# PROC106B_FLASH_USB_TO_UART.net
KiCad netlist of a schematic drawn in Altium Designer
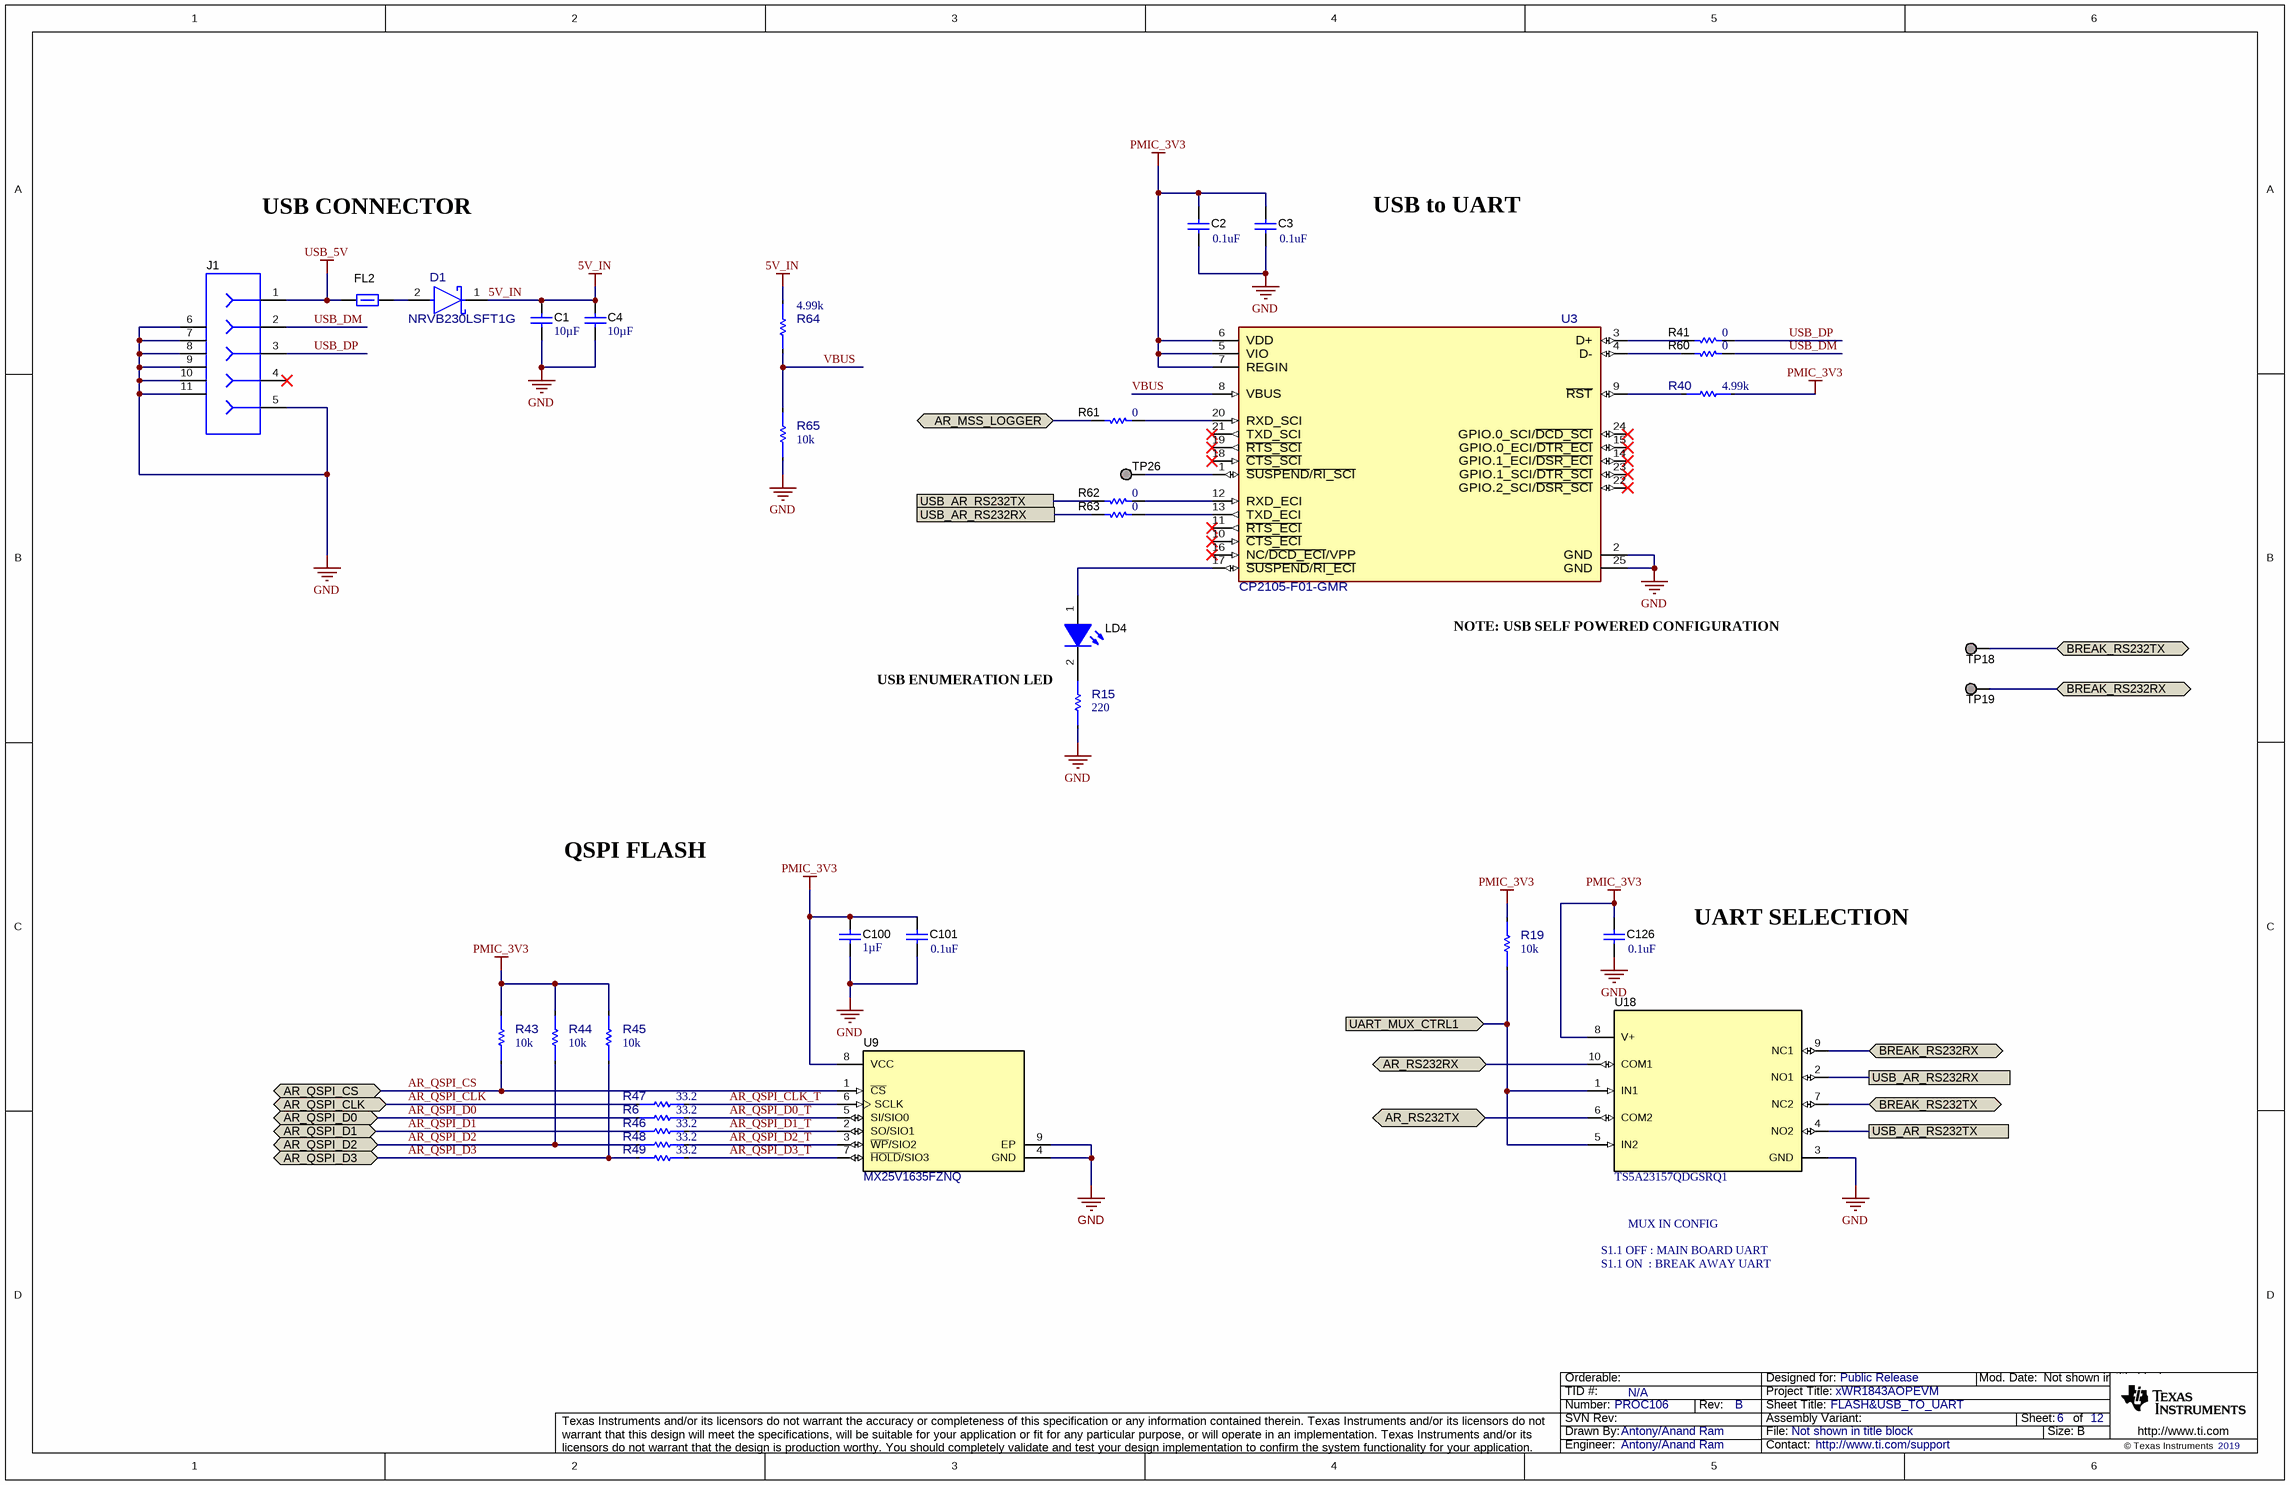
[diagram p0: PROC106B_FLASH_USB_TO_UART.SchDoc]

(export (version "E")
  (design (tool "Eeschema 10.0.6"))
  (components
    (comp (ref "C1")
      (value "GCM21BR71A106KE22L")
      (footprint "0805L")
      (description "CAP, CERM, 10 uF, 10 V, +/- 10%, X7R, 0805")
      (fields
        (field (name "CAP_F") "10µF")
        (field (name "MANUFACTURER") "MuRata")
        (field (name "PUBLISHER") "Texas Instruments")
      )
      (libsource (lib "Altium Vault - TI") (part "Capacitor"))
    )
    (comp (ref "C2")
      (value "GCM155R71C104KA55D")
      (footprint "0402L")
      (description "CAP, CERM, 0.1 uF, 16 V, +/- 10%, X7R, 0402")
      (fields
        (field (name "MANUFACTURER") "MuRata")
        (field (name "VALUEDISPLAYED") "0.1uF")
        (field (name "PUBLISHER") "Texas Instruments")
      )
      (libsource (lib "Altium Vault - TI") (part "Capacitor"))
    )
    (comp (ref "C3")
      (value "GCM155R71C104KA55D")
      (footprint "0402L")
      (description "CAP, CERM, 0.1 uF, 16 V, +/- 10%, X7R, 0402")
      (fields
        (field (name "MANUFACTURER") "MuRata")
        (field (name "VALUEDISPLAYED") "0.1uF")
        (field (name "PUBLISHER") "Texas Instruments")
      )
      (libsource (lib "Altium Vault - TI") (part "Capacitor"))
    )
    (comp (ref "C4")
      (value "GCM21BR71A106KE22L")
      (footprint "0805L")
      (description "CAP, CERM, 10 uF, 10 V, +/- 10%, X7R, 0805")
      (fields
        (field (name "CAP_F") "10µF")
        (field (name "MANUFACTURER") "MuRata")
        (field (name "PUBLISHER") "Texas Instruments")
      )
      (libsource (lib "Altium Vault - TI") (part "Capacitor"))
    )
    (comp (ref "C100")
      (value "GCM188R71C105KA64D")
      (footprint "0603L")
      (description "CAP, CERM, 1 uF, 16 V, +/- 10%, X7R, AEC-Q200 Grade 1, 0603")
      (fields
        (field (name "CAP_F") "1µF")
        (field (name "MANUFACTURER") "MuRata")
        (field (name "PUBLISHER") "Texas Instruments")
      )
      (libsource (lib "Altium Vault - TI") (part "Capacitor"))
    )
    (comp (ref "C101")
      (value "GCM155R71C104KA55D")
      (footprint "0402L")
      (description "CAP, CERM, 0.1 uF, 16 V, +/- 10%, X7R, 0402")
      (fields
        (field (name "MANUFACTURER") "MuRata")
        (field (name "VALUEDISPLAYED") "0.1uF")
        (field (name "PUBLISHER") "Texas Instruments")
      )
      (libsource (lib "Altium Vault - TI") (part "Capacitor"))
    )
    (comp (ref "C126")
      (value "GCM155R71C104KA55D")
      (footprint "0402L")
      (description "CAP, CERM, 0.1 uF, 16 V, +/- 10%, X7R, 0402")
      (fields
        (field (name "MANUFACTURER") "MuRata")
        (field (name "VALUEDISPLAYED") "0.1uF")
        (field (name "PUBLISHER") "Texas Instruments")
      )
      (libsource (lib "Altium Vault - TI") (part "Capacitor"))
    )
    (comp (ref "D1")
      (value "NRVB230LSFT1G")
      (footprint "FP-NRVB230LSFT1G_SOD-123F-MFG")
      (description "Diode Schottky 30V 2A Surface Mount SOD-123FL")
      (fields
        (field (name "MANUFACTURER") "ON Semiconductor")
        (field (name "DIGIKEY PART NUMBER") "NRVB230LSFT1GOSCT-ND")
      )
      (libsource (lib "Altium Vault - TI") (part "SYM-NRVB230LSFT1G"))
    )
    (comp (ref "FL2")
      (value "BLM15PD300SZ1D")
      (footprint "0402L")
      (description "Inductor, Ferrite Bead, Ferrite, 2.2 A, 0.035 ohm, AEC-Q200 Grade 1, SMD")
      (fields (field (name "MANUFACTURER") "MuRata") (field (name "PUBLISHER") "Texas Instruments"))
      (libsource (lib "Altium Vault - TI") (part "Ferrite_Bead"))
    )
    (comp (ref "J1")
      (value "105017-0001")
      (footprint "CONN_105017-0001")
      (description "Connector, Receptacle, Micro-USB Type B, R/A, Bottom Mount SMT")
      (fields (field (name "MANUFACTURER") "Molex") (field (name "PUBLISHER") "Texas Instruments"))
      (libsource (lib "Altium Vault - TI") (part "CONN_105017-0001"))
    )
    (comp (ref "LD4")
      (value "APHHS1005CGCK")
      (footprint "APHHS1005_Green")
      (description "LED, Green, SMD")
      (fields (field (name "MANUFACTURER") "Kingbright"))
      (libsource (lib "Altium Vault - TI") (part "LED"))
    )
    (comp (ref "R6")
      (value "33.2")
      (footprint "FP-ERJ-1GNF33R2C_0201-IPC_C")
      (description "Res Thick Film 0201 33.2 Ohm 1% 0.05W(1/20W) ±200ppm/C Pad SMD Automotive T/R")
      (fields (field (name "MANUFACTURER") "Panasonic") (field (name "PARTNUMBER") "ERJ-1GNF33R2C"))
      (libsource (lib "Altium Vault - TI") (part "SYM-ERJ-1GNF33R2C"))
    )
    (comp (ref "R15")
      (value "220")
      (footprint "FP-ERJ-1GNJ221C_0201-IPC_C")
      (description "220 Ohms ±5% 0.05W, 1/20W Chip Resistor 0201 (0603 Metric) Automotive AEC-Q200 Thick Film")
      (fields
        (field (name "MANUFACTURER") "Panasonic Electronic Components")
        (field (name "PARTNUMBER") "ERJ-1GNJ221C")
      )
      (libsource (lib "Altium Vault - TI") (part "SYM-ERJ-1GNJ221C"))
    )
    (comp (ref "R19")
      (value "10k")
      (footprint "FP-ERA-1AEB103C_0201-IPC_C")
      (description "RES SMD 10K OHM 0.1% 1/20W 0201")
      (fields (field (name "MANUFACTURER") "Panasonic") (field (name "PARTNUMBER") "ERA-1AEB103C"))
      (libsource (lib "Altium Vault - TI") (part "SYM-ERA-1AEB103C"))
    )
    (comp (ref "R40")
      (value "4.99k")
      (footprint "FP-ERJ-1GNF4991C_0201-IPC_C")
      (description "4.99 kOhms ±1% 0.05W, 1/20W Chip Resistor 0201 (0603 Metric) Automotive AEC-Q200 Thick Film")
      (fields
        (field (name "MANUFACTURER") "Panasonic Electronic Components")
        (field (name "PARTNUMBER") "ERJ-1GNF4991C")
      )
      (libsource (lib "Altium Vault - TI") (part "SYM-ERJ-1GNF4991C"))
    )
    (comp (ref "R41")
      (value "ERJ-1GN0R00C")
      (footprint "0201L")
      (description "RES, 0, 5%, .05 W, AEC-Q200 Grade 0, 0201")
      (fields
        (field (name "MANUFACTURER") "Panasonic")
        (field (name "VALUEDISPLAYED") "0")
        (field (name "PUBLISHER") "Texas Instruments")
      )
      (libsource (lib "Altium Vault - TI") (part "Resistor"))
    )
    (comp (ref "R43")
      (value "10k")
      (footprint "FP-ERA-1AEB103C_0201-IPC_C")
      (description "RES SMD 10K OHM 0.1% 1/20W 0201")
      (fields (field (name "MANUFACTURER") "Panasonic") (field (name "PARTNUMBER") "ERA-1AEB103C"))
      (libsource (lib "Altium Vault - TI") (part "SYM-ERA-1AEB103C"))
    )
    (comp (ref "R44")
      (value "10k")
      (footprint "FP-ERA-1AEB103C_0201-IPC_C")
      (description "RES SMD 10K OHM 0.1% 1/20W 0201")
      (fields (field (name "MANUFACTURER") "Panasonic") (field (name "PARTNUMBER") "ERA-1AEB103C"))
      (libsource (lib "Altium Vault - TI") (part "SYM-ERA-1AEB103C"))
    )
    (comp (ref "R45")
      (value "10k")
      (footprint "FP-ERA-1AEB103C_0201-IPC_C")
      (description "RES SMD 10K OHM 0.1% 1/20W 0201")
      (fields (field (name "MANUFACTURER") "Panasonic") (field (name "PARTNUMBER") "ERA-1AEB103C"))
      (libsource (lib "Altium Vault - TI") (part "SYM-ERA-1AEB103C"))
    )
    (comp (ref "R46")
      (value "33.2")
      (footprint "FP-ERJ-1GNF33R2C_0201-IPC_C")
      (description "Res Thick Film 0201 33.2 Ohm 1% 0.05W(1/20W) ±200ppm/C Pad SMD Automotive T/R")
      (fields (field (name "MANUFACTURER") "Panasonic") (field (name "PARTNUMBER") "ERJ-1GNF33R2C"))
      (libsource (lib "Altium Vault - TI") (part "SYM-ERJ-1GNF33R2C"))
    )
    (comp (ref "R47")
      (value "33.2")
      (footprint "FP-ERJ-1GNF33R2C_0201-IPC_C")
      (description "Res Thick Film 0201 33.2 Ohm 1% 0.05W(1/20W) ±200ppm/C Pad SMD Automotive T/R")
      (fields (field (name "MANUFACTURER") "Panasonic") (field (name "PARTNUMBER") "ERJ-1GNF33R2C"))
      (libsource (lib "Altium Vault - TI") (part "SYM-ERJ-1GNF33R2C"))
    )
    (comp (ref "R48")
      (value "33.2")
      (footprint "FP-ERJ-1GNF33R2C_0201-IPC_C")
      (description "Res Thick Film 0201 33.2 Ohm 1% 0.05W(1/20W) ±200ppm/C Pad SMD Automotive T/R")
      (fields (field (name "MANUFACTURER") "Panasonic") (field (name "PARTNUMBER") "ERJ-1GNF33R2C"))
      (libsource (lib "Altium Vault - TI") (part "SYM-ERJ-1GNF33R2C"))
    )
    (comp (ref "R49")
      (value "33.2")
      (footprint "FP-ERJ-1GNF33R2C_0201-IPC_C")
      (description "Res Thick Film 0201 33.2 Ohm 1% 0.05W(1/20W) ±200ppm/C Pad SMD Automotive T/R")
      (fields (field (name "MANUFACTURER") "Panasonic") (field (name "PARTNUMBER") "ERJ-1GNF33R2C"))
      (libsource (lib "Altium Vault - TI") (part "SYM-ERJ-1GNF33R2C"))
    )
    (comp (ref "R60")
      (value "ERJ-1GN0R00C")
      (footprint "0201L")
      (description "RES, 0, 5%, .05 W, AEC-Q200 Grade 0, 0201")
      (fields
        (field (name "MANUFACTURER") "Panasonic")
        (field (name "VALUEDISPLAYED") "0")
        (field (name "PUBLISHER") "Texas Instruments")
      )
      (libsource (lib "Altium Vault - TI") (part "Resistor"))
    )
    (comp (ref "R61")
      (value "ERJ-1GN0R00C")
      (footprint "0201L")
      (description "RES, 0, 5%, .05 W, AEC-Q200 Grade 0, 0201")
      (fields
        (field (name "MANUFACTURER") "Panasonic")
        (field (name "VALUEDISPLAYED") "0")
        (field (name "PUBLISHER") "Texas Instruments")
      )
      (libsource (lib "Altium Vault - TI") (part "Resistor"))
    )
    (comp (ref "R62")
      (value "ERJ-1GN0R00C")
      (footprint "0201L")
      (description "RES, 0, 5%, .05 W, AEC-Q200 Grade 0, 0201")
      (fields
        (field (name "MANUFACTURER") "Panasonic")
        (field (name "VALUEDISPLAYED") "0")
        (field (name "PUBLISHER") "Texas Instruments")
      )
      (libsource (lib "Altium Vault - TI") (part "Resistor"))
    )
    (comp (ref "R63")
      (value "ERJ-1GN0R00C")
      (footprint "0201L")
      (description "RES, 0, 5%, .05 W, AEC-Q200 Grade 0, 0201")
      (fields
        (field (name "MANUFACTURER") "Panasonic")
        (field (name "VALUEDISPLAYED") "0")
        (field (name "PUBLISHER") "Texas Instruments")
      )
      (libsource (lib "Altium Vault - TI") (part "Resistor"))
    )
    (comp (ref "R64")
      (value "4.99k")
      (footprint "FP-ERJ-1GNF4991C_0201-IPC_C")
      (description "4.99 kOhms ±1% 0.05W, 1/20W Chip Resistor 0201 (0603 Metric) Automotive AEC-Q200 Thick Film")
      (fields
        (field (name "MANUFACTURER") "Panasonic Electronic Components")
        (field (name "PARTNUMBER") "ERJ-1GNF4991C")
      )
      (libsource (lib "Altium Vault - TI") (part "SYM-ERJ-1GNF4991C"))
    )
    (comp (ref "R65")
      (value "10k")
      (footprint "FP-ERA-1AEB103C_0201-IPC_C")
      (description "RES SMD 10K OHM 0.1% 1/20W 0201")
      (fields (field (name "MANUFACTURER") "Panasonic") (field (name "PARTNUMBER") "ERA-1AEB103C"))
      (libsource (lib "Altium Vault - TI") (part "SYM-ERA-1AEB103C"))
    )
    (comp (ref "TP18")
      (value "TESTPOINT")
      (footprint "TP_25MIL-SMT")
      (description "TEST POINT.  No entry in BOM.")
      (libsource (lib "Altium Vault - TI") (part "TESTPOINT"))
    )
    (comp (ref "TP19")
      (value "TESTPOINT")
      (footprint "TP_25MIL-SMT")
      (description "TEST POINT.  No entry in BOM.")
      (libsource (lib "Altium Vault - TI") (part "TESTPOINT"))
    )
    (comp (ref "TP26")
      (value "TESTPOINT")
      (footprint "TP_25MIL-SMT")
      (description "TEST POINT.  No entry in BOM.")
      (libsource (lib "Altium Vault - TI") (part "TESTPOINT"))
    )
    (comp (ref "U3")
      (value "CP2105-F01-GMR")
      (footprint "FP-CP2105-F01-GMR_QFN24-EP-IPC_A")
      (description "I/O Controller Interface IC USB to Dual UART bridge")
      (fields (field (name "MANUFACTURER") "Silicon Labs"))
      (libsource (lib "Altium Vault - TI") (part "SYM-CP2105-F01-GMR"))
    )
    (comp (ref "U9")
      (value "MX25V1635FZNQ")
      (footprint "WSON-8L_6x5MM_EP")
      (description "2.3V-3.6V, 16M-BIT [x 1/x 2/x 4] CMOS FLASH Memory, WSON-8")
      (fields (field (name "MANUFACTURER") "Macronix International Co., LTD"))
      (libsource (lib "Altium Vault - TI") (part "MX25V1635FZ"))
    )
    (comp (ref "U18")
      (value "TS5A23157QDGSRQ1")
      (footprint "DGS0010A_L")
      (description "Automotive Catalog Dual 15-Ohm SPDT Analog Switch, DGS0010A (VSSOP-10)")
      (fields
        (field (name "MANUFACTURER") "Texas Instruments")
        (field (name "PARTNUMBER") "TS5A23157QDGSRQ1")
        (field (name "PUBLISHER") "Texas Instruments")
      )
      (libsource (lib "Altium Vault - TI") (part "TS5A23159"))
    )
  )
  (nets
    (net (code "1") (name "/AR_MSS_LOGGER") (class "Default")
      (node (ref "R61") (pin "1") (pinfunction "1_1") (pintype "passive"))
    )
    (net (code "2") (name "/AR_QSPI_CLK") (class "Default")
      (node (ref "R47") (pin "1") (pinfunction "1_1") (pintype "passive"))
    )
    (net (code "3") (name "/AR_QSPI_CLK_T") (class "Default")
      (node (ref "R47") (pin "2") (pinfunction "2_2") (pintype "passive"))
      (node (ref "U9") (pin "6") (pinfunction "SCLK_6") (pintype "input"))
    )
    (net (code "4") (name "/AR_QSPI_CS") (class "Default")
      (node (ref "R43") (pin "1") (pinfunction "1_1") (pintype "passive"))
      (node (ref "U9") (pin "1") (pinfunction "CS_1") (pintype "input"))
    )
    (net (code "5") (name "/AR_QSPI_D0") (class "Default")
      (node (ref "R6") (pin "1") (pinfunction "1_1") (pintype "passive"))
    )
    (net (code "6") (name "/AR_QSPI_D0_T") (class "Default")
      (node (ref "R6") (pin "2") (pinfunction "2_2") (pintype "passive"))
      (node (ref "U9") (pin "5") (pinfunction "SI/SIO0_5") (pintype "bidirectional"))
    )
    (net (code "7") (name "/AR_QSPI_D1") (class "Default")
      (node (ref "R46") (pin "1") (pinfunction "1_1") (pintype "passive"))
    )
    (net (code "8") (name "/AR_QSPI_D1_T") (class "Default")
      (node (ref "R46") (pin "2") (pinfunction "2_2") (pintype "passive"))
      (node (ref "U9") (pin "2") (pinfunction "SO/SIO1_2") (pintype "bidirectional"))
    )
    (net (code "9") (name "/AR_QSPI_D2") (class "Default")
      (node (ref "R44") (pin "1") (pinfunction "1_1") (pintype "passive"))
      (node (ref "R48") (pin "1") (pinfunction "1_1") (pintype "passive"))
    )
    (net (code "10") (name "/AR_QSPI_D2_T") (class "Default")
      (node (ref "R48") (pin "2") (pinfunction "2_2") (pintype "passive"))
      (node (ref "U9") (pin "3") (pinfunction "~{WP}/SIO2_3") (pintype "bidirectional"))
    )
    (net (code "11") (name "/AR_QSPI_D3") (class "Default")
      (node (ref "R45") (pin "1") (pinfunction "1_1") (pintype "passive"))
      (node (ref "R49") (pin "1") (pinfunction "1_1") (pintype "passive"))
    )
    (net (code "12") (name "/AR_QSPI_D3_T") (class "Default")
      (node (ref "R49") (pin "2") (pinfunction "2_2") (pintype "passive"))
      (node (ref "U9") (pin "7") (pinfunction "~{HOLD}/SIO3_7") (pintype "bidirectional"))
    )
    (net (code "13") (name "/AR_RS232RX") (class "Default")
      (node (ref "U18") (pin "10") (pinfunction "COM1_10") (pintype "bidirectional"))
    )
    (net (code "14") (name "/AR_RS232TX") (class "Default")
      (node (ref "U18") (pin "6") (pinfunction "COM2_6") (pintype "bidirectional"))
    )
    (net (code "15") (name "/BREAK_RS232RX") (class "Default")
      (node (ref "TP19") (pin "1") (pintype "passive"))
      (node (ref "U18") (pin "9") (pinfunction "NC1_9") (pintype "bidirectional"))
    )
    (net (code "16") (name "/BREAK_RS232TX") (class "Default")
      (node (ref "TP18") (pin "1") (pintype "passive"))
      (node (ref "U18") (pin "7") (pinfunction "NC2_7") (pintype "bidirectional"))
    )
    (net (code "17") (name "/UART_MUX_CTRL1") (class "Default")
      (node (ref "R19") (pin "1") (pinfunction "1_1") (pintype "passive"))
      (node (ref "U18") (pin "1") (pinfunction "IN1_1") (pintype "input"))
      (node (ref "U18") (pin "5") (pinfunction "IN2_5") (pintype "input"))
    )
    (net (code "18") (name "/USB_AR_RS232RX") (class "Default")
      (node (ref "R63") (pin "1") (pinfunction "1_1") (pintype "passive"))
      (node (ref "U18") (pin "2") (pinfunction "NO1_2") (pintype "bidirectional"))
    )
    (net (code "19") (name "/USB_AR_RS232TX") (class "Default")
      (node (ref "R62") (pin "1") (pinfunction "1_1") (pintype "passive"))
      (node (ref "U18") (pin "4") (pinfunction "NO2_4") (pintype "bidirectional"))
    )
    (net (code "20") (name "/USB_DM") (class "Default")
      (node (ref "J1") (pin "2") (pintype "passive"))
      (node (ref "R60") (pin "2") (pinfunction "2_2") (pintype "passive"))
    )
    (net (code "21") (name "/USB_DP") (class "Default")
      (node (ref "J1") (pin "3") (pintype "passive"))
      (node (ref "R41") (pin "2") (pinfunction "2_2") (pintype "passive"))
    )
    (net (code "22") (name "/VBUS") (class "Default")
      (node (ref "R64") (pin "2") (pinfunction "2_2") (pintype "passive"))
      (node (ref "R65") (pin "2") (pinfunction "2_2") (pintype "passive"))
      (node (ref "U3") (pin "8") (pinfunction "VBUS_8") (pintype "input"))
    )
    (net (code "23") (name "5V_IN") (class "Default")
      (node (ref "C1") (pin "2") (pinfunction "2_2") (pintype "passive"))
      (node (ref "C4") (pin "1") (pinfunction "1_1") (pintype "passive"))
      (node (ref "D1") (pin "1") (pinfunction "CATHODE_1") (pintype "passive"))
      (node (ref "R64") (pin "1") (pinfunction "1_1") (pintype "passive"))
    )
    (net (code "24") (name "GND") (class "Default")
      (node (ref "C1") (pin "1") (pinfunction "1_1") (pintype "passive"))
      (node (ref "C100") (pin "1") (pinfunction "1_1") (pintype "passive"))
      (node (ref "C101") (pin "1") (pinfunction "1_1") (pintype "passive"))
      (node (ref "C126") (pin "1") (pinfunction "1_1") (pintype "passive"))
      (node (ref "C2") (pin "2") (pinfunction "2_2") (pintype "passive"))
      (node (ref "C3") (pin "2") (pinfunction "2_2") (pintype "passive"))
      (node (ref "C4") (pin "2") (pinfunction "2_2") (pintype "passive"))
      (node (ref "J1") (pin "10") (pintype "passive"))
      (node (ref "J1") (pin "11") (pintype "passive"))
      (node (ref "J1") (pin "5") (pintype "passive"))
      (node (ref "J1") (pin "6") (pintype "passive"))
      (node (ref "J1") (pin "7") (pintype "passive"))
      (node (ref "J1") (pin "8") (pintype "passive"))
      (node (ref "J1") (pin "9") (pintype "passive"))
      (node (ref "R15") (pin "1") (pinfunction "1_1") (pintype "passive"))
      (node (ref "R65") (pin "1") (pinfunction "1_1") (pintype "passive"))
      (node (ref "U18") (pin "3") (pinfunction "GND_3") (pintype "power_in"))
      (node (ref "U3") (pin "2") (pinfunction "GND_2") (pintype "power_in"))
      (node (ref "U3") (pin "25") (pinfunction "GND_25") (pintype "power_in"))
      (node (ref "U9") (pin "4") (pinfunction "GND_4") (pintype "power_in"))
      (node (ref "U9") (pin "9") (pinfunction "EP_9") (pintype "passive"))
    )
    (net (code "25") (name "Net-(D1-ANODE)") (class "Default")
      (node (ref "D1") (pin "2") (pinfunction "ANODE_2") (pintype "passive"))
      (node (ref "FL2") (pin "2") (pinfunction "2_2") (pintype "passive"))
    )
    (net (code "26") (name "Net-(LD4-A)") (class "Default")
      (node (ref "LD4") (pin "1") (pinfunction "A_1") (pintype "passive"))
      (node (ref "U3") (pin "17") (pinfunction "~{SUSPEND}/~{RI_ECI}_17") (pintype "bidirectional"))
    )
    (net (code "27") (name "Net-(LD4-K)") (class "Default")
      (node (ref "LD4") (pin "2") (pinfunction "K_2") (pintype "passive"))
      (node (ref "R15") (pin "2") (pinfunction "2_2") (pintype "passive"))
    )
    (net (code "28") (name "Net-(U3-D+)") (class "Default")
      (node (ref "R41") (pin "1") (pinfunction "1_1") (pintype "passive"))
      (node (ref "U3") (pin "3") (pinfunction "D+_3") (pintype "bidirectional"))
    )
    (net (code "29") (name "Net-(U3-D-)") (class "Default")
      (node (ref "R60") (pin "1") (pinfunction "1_1") (pintype "passive"))
      (node (ref "U3") (pin "4") (pinfunction "D-_4") (pintype "bidirectional"))
    )
    (net (code "30") (name "Net-(U3-RXD_ECI)") (class "Default")
      (node (ref "R62") (pin "2") (pinfunction "2_2") (pintype "passive"))
      (node (ref "U3") (pin "12") (pinfunction "RXD_ECI_12") (pintype "input"))
    )
    (net (code "31") (name "Net-(U3-RXD_SCI)") (class "Default")
      (node (ref "R61") (pin "2") (pinfunction "2_2") (pintype "passive"))
      (node (ref "U3") (pin "20") (pinfunction "RXD_SCI_20") (pintype "input"))
    )
    (net (code "32") (name "Net-(U3-TXD_ECI)") (class "Default")
      (node (ref "R63") (pin "2") (pinfunction "2_2") (pintype "passive"))
      (node (ref "U3") (pin "13") (pinfunction "TXD_ECI_13") (pintype "output"))
    )
    (net (code "33") (name "Net-(U3-~{RST})") (class "Default")
      (node (ref "R40") (pin "2") (pinfunction "2_2") (pintype "passive"))
      (node (ref "U3") (pin "9") (pinfunction "~{RST}_9") (pintype "bidirectional"))
    )
    (net (code "34") (name "Net-(U3-~{SUSPEND}{slash}~{RI_SCI})") (class "Default")
      (node (ref "TP26") (pin "1") (pintype "passive"))
      (node (ref "U3") (pin "1") (pinfunction "~{SUSPEND}/~{RI_SCI}_1") (pintype "bidirectional"))
    )
    (net (code "35") (name "PMIC_3V3") (class "Default")
      (node (ref "C100") (pin "2") (pinfunction "2_2") (pintype "passive"))
      (node (ref "C101") (pin "2") (pinfunction "2_2") (pintype "passive"))
      (node (ref "C126") (pin "2") (pinfunction "2_2") (pintype "passive"))
      (node (ref "C2") (pin "1") (pinfunction "1_1") (pintype "passive"))
      (node (ref "C3") (pin "1") (pinfunction "1_1") (pintype "passive"))
      (node (ref "R19") (pin "2") (pinfunction "2_2") (pintype "passive"))
      (node (ref "R40") (pin "1") (pinfunction "1_1") (pintype "passive"))
      (node (ref "R43") (pin "2") (pinfunction "2_2") (pintype "passive"))
      (node (ref "R44") (pin "2") (pinfunction "2_2") (pintype "passive"))
      (node (ref "R45") (pin "2") (pinfunction "2_2") (pintype "passive"))
      (node (ref "U18") (pin "8") (pinfunction "V+_8") (pintype "power_in"))
      (node (ref "U3") (pin "5") (pinfunction "VIO_5") (pintype "power_in"))
      (node (ref "U3") (pin "6") (pinfunction "VDD_6") (pintype "power_in"))
      (node (ref "U3") (pin "7") (pinfunction "REGIN_7") (pintype "power_in"))
      (node (ref "U9") (pin "8") (pinfunction "VCC_8") (pintype "power_in"))
    )
    (net (code "36") (name "USB_5V") (class "Default")
      (node (ref "FL2") (pin "1") (pinfunction "1_1") (pintype "passive"))
      (node (ref "J1") (pin "1") (pintype "passive"))
    )
    (net (code "37") (name "unconnected-(J1-Pad4)") (class "Default")
      (node (ref "J1") (pin "4") (pintype "passive+no_connect"))
    )
    (net (code "38") (name "unconnected-(U3-GPIO.0_ECI{slash}~{DTR_ECI}-Pad15)") (class "Default")
      (node (ref "U3") (pin "15") (pinfunction "GPIO.0_ECI/~{DTR_ECI}_15") (pintype "bidirectional+no_connect"))
    )
    (net (code "39") (name "unconnected-(U3-GPIO.0_SCI{slash}~{DCD_SCI}-Pad24)") (class "Default")
      (node (ref "U3") (pin "24") (pinfunction "GPIO.0_SCI/~{DCD_SCI}_24") (pintype "bidirectional+no_connect"))
    )
    (net (code "40") (name "unconnected-(U3-GPIO.1_ECI{slash}~{DSR_ECI}-Pad14)") (class "Default")
      (node (ref "U3") (pin "14") (pinfunction "GPIO.1_ECI/~{DSR_ECI}_14") (pintype "bidirectional+no_connect"))
    )
    (net (code "41") (name "unconnected-(U3-GPIO.1_SCI{slash}~{DTR_SCI}-Pad23)") (class "Default")
      (node (ref "U3") (pin "23") (pinfunction "GPIO.1_SCI/~{DTR_SCI}_23") (pintype "bidirectional+no_connect"))
    )
    (net (code "42") (name "unconnected-(U3-GPIO.2_SCI{slash}~{DSR_SCI}-Pad22)") (class "Default")
      (node (ref "U3") (pin "22") (pinfunction "GPIO.2_SCI/~{DSR_SCI}_22") (pintype "bidirectional+no_connect"))
    )
    (net (code "43") (name "unconnected-(U3-NC{slash}~{DCD_ECI}{slash}VPP-Pad16)") (class "Default")
      (node (ref "U3") (pin "16") (pinfunction "NC/~{DCD_ECI}/VPP_16") (pintype "input+no_connect"))
    )
    (net (code "44") (name "unconnected-(U3-TXD_SCI-Pad21)") (class "Default")
      (node (ref "U3") (pin "21") (pinfunction "TXD_SCI_21") (pintype "output+no_connect"))
    )
    (net (code "45") (name "unconnected-(U3-~{CTS_ECI}-Pad10)") (class "Default")
      (node (ref "U3") (pin "10") (pinfunction "~{CTS_ECI}_10") (pintype "input+no_connect"))
    )
    (net (code "46") (name "unconnected-(U3-~{CTS_SCI}-Pad18)") (class "Default")
      (node (ref "U3") (pin "18") (pinfunction "~{CTS_SCI}_18") (pintype "input+no_connect"))
    )
    (net (code "47") (name "unconnected-(U3-~{RTS_ECI}-Pad11)") (class "Default")
      (node (ref "U3") (pin "11") (pinfunction "~{RTS_ECI}_11") (pintype "output+no_connect"))
    )
    (net (code "48") (name "unconnected-(U3-~{RTS_SCI}-Pad19)") (class "Default")
      (node (ref "U3") (pin "19") (pinfunction "~{RTS_SCI}_19") (pintype "output+no_connect"))
    )
  )
)
